# QCopterRCs_Sch.net
KiCad netlist of a schematic drawn in Altium Designer
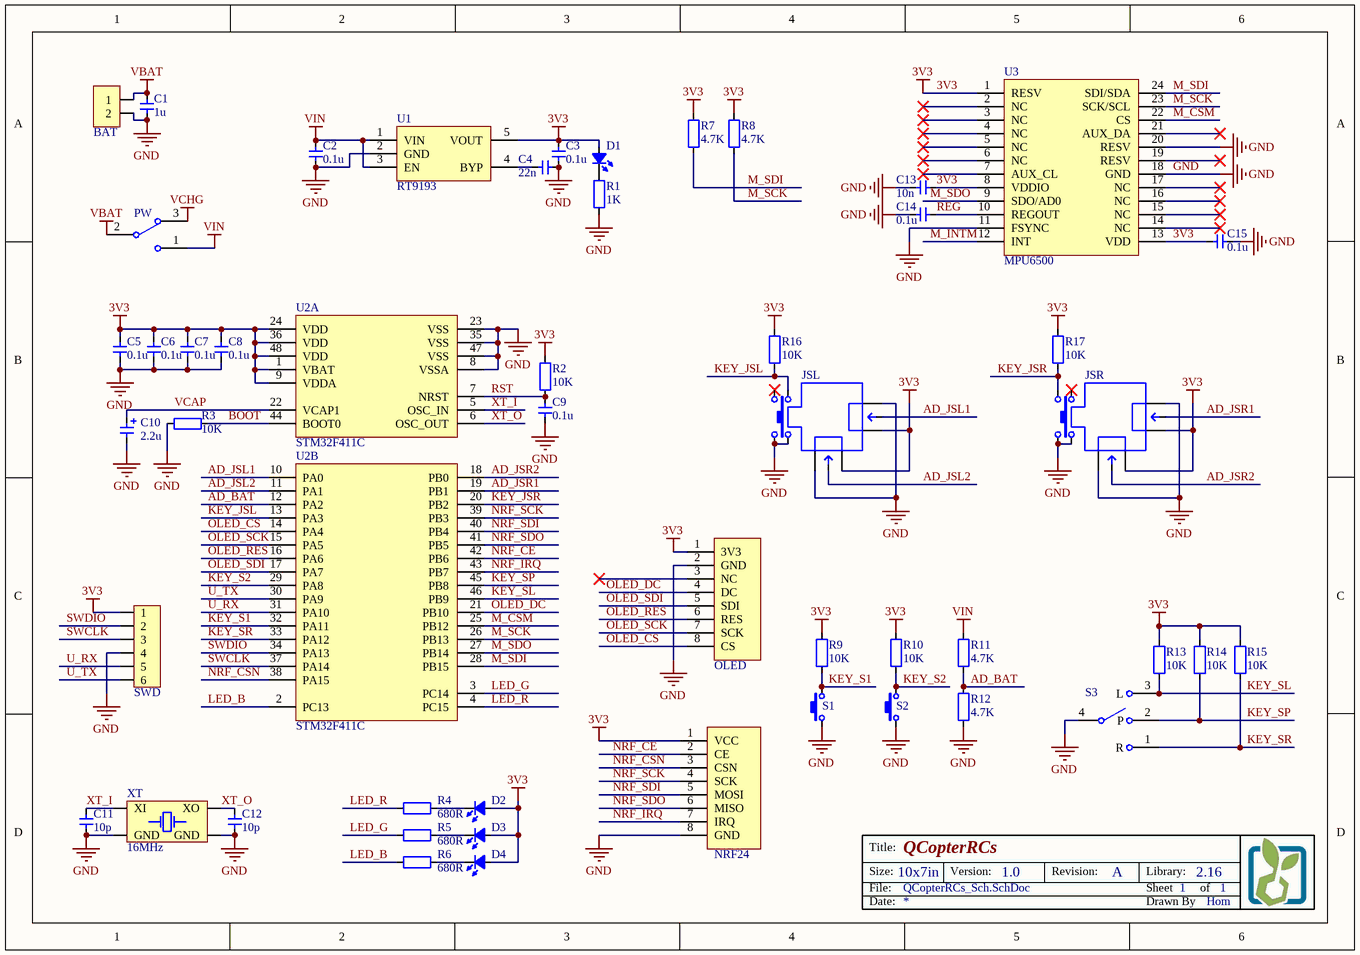
[diagram p0: QCopterRCs_Sch.SchDoc]

(export (version "E")
  (design (tool "Eeschema 10.0.6"))
  (components
    (comp (ref "BAT")
      (value "MX1.25_2P")
      (footprint "PCB_Connector:MX1.25_S90_2P")
      (description "MX")
      (libsource (lib "SCH_Connector") (part "MX1.25_2P"))
    )
    (comp (ref "C1")
      (value "1u")
      (footprint "PCB_PassiveCap:CAP_0603")
      (description "Capacitor")
      (fields (field (name "Comment") "Cap_0603"))
      (libsource (lib "SCH_Passive") (part "Cap_0603"))
    )
    (comp (ref "C2")
      (value "0.1u")
      (footprint "PCB_PassiveCap:CAP_0603")
      (description "Capacitor")
      (fields (field (name "Comment") "Cap_0603"))
      (libsource (lib "SCH_Passive") (part "Cap_0603"))
    )
    (comp (ref "C3")
      (value "0.1u")
      (footprint "PCB_PassiveCap:CAP_0603")
      (description "Capacitor")
      (fields (field (name "Comment") "Cap_0603"))
      (libsource (lib "SCH_Passive") (part "Cap_0603"))
    )
    (comp (ref "C4")
      (value "22n")
      (footprint "PCB_PassiveCap:CAP_0603")
      (description "Capacitor")
      (fields (field (name "Comment") "Cap_0603"))
      (libsource (lib "SCH_Passive") (part "Cap_0603"))
    )
    (comp (ref "C5")
      (value "0.1u")
      (footprint "PCB_PassiveCap:CAP_0603")
      (description "Capacitor")
      (fields (field (name "Comment") "Cap_0603"))
      (libsource (lib "SCH_Passive") (part "Cap_0603"))
    )
    (comp (ref "C6")
      (value "0.1u")
      (footprint "PCB_PassiveCap:CAP_0603")
      (description "Capacitor")
      (fields (field (name "Comment") "Cap_0603"))
      (libsource (lib "SCH_Passive") (part "Cap_0603"))
    )
    (comp (ref "C7")
      (value "0.1u")
      (footprint "PCB_PassiveCap:CAP_0603")
      (description "Capacitor")
      (fields (field (name "Comment") "Cap_0603"))
      (libsource (lib "SCH_Passive") (part "Cap_0603"))
    )
    (comp (ref "C8")
      (value "0.1u")
      (footprint "PCB_PassiveCap:CAP_0603")
      (description "Capacitor")
      (fields (field (name "Comment") "Cap_0603"))
      (libsource (lib "SCH_Passive") (part "Cap_0603"))
    )
    (comp (ref "C9")
      (value "0.1u")
      (footprint "PCB_PassiveCap:CAP_0603")
      (description "Capacitor")
      (fields (field (name "Comment") "Cap_0603"))
      (libsource (lib "SCH_Passive") (part "Cap_0603"))
    )
    (comp (ref "C10")
      (value "2.2u")
      (footprint "PCB_PassiveCap:CAP_TAN_P0805")
      (description "Capacitor")
      (fields (field (name "Comment") "Cap_Tan_0805"))
      (libsource (lib "SCH_Passive") (part "Cap_Tan_0805"))
    )
    (comp (ref "C11")
      (value "10p")
      (footprint "PCB_PassiveCap:CAP_0603")
      (description "Capacitor")
      (fields (field (name "Comment") "Cap_0603"))
      (libsource (lib "SCH_Passive") (part "Cap_0603"))
    )
    (comp (ref "C12")
      (value "10p")
      (footprint "PCB_PassiveCap:CAP_0603")
      (description "Capacitor")
      (fields (field (name "Comment") "Cap_0603"))
      (libsource (lib "SCH_Passive") (part "Cap_0603"))
    )
    (comp (ref "C13")
      (value "10n")
      (footprint "PCB_PassiveCap:CAP_0603")
      (description "Capacitor")
      (fields (field (name "Comment") "Cap_0603"))
      (libsource (lib "SCH_Passive") (part "Cap_0603"))
    )
    (comp (ref "C14")
      (value "0.1u")
      (footprint "PCB_PassiveCap:CAP_0603")
      (description "Capacitor")
      (fields (field (name "Comment") "Cap_0603"))
      (libsource (lib "SCH_Passive") (part "Cap_0603"))
    )
    (comp (ref "C15")
      (value "0.1u")
      (footprint "PCB_PassiveCap:CAP_0603")
      (description "Capacitor")
      (fields (field (name "Comment") "Cap_0603"))
      (libsource (lib "SCH_Passive") (part "Cap_0603"))
    )
    (comp (ref "D1")
      (value "LED_0603")
      (footprint "PCB_ActiveLED:LED_0603_YELLOW")
      (description "LED")
      (libsource (lib "SCH_Active") (part "LED_0603"))
    )
    (comp (ref "D2")
      (value "LED_0805")
      (footprint "PCB_ActiveLED:LED_0805_RED")
      (description "LED")
      (libsource (lib "SCH_Active") (part "LED_0805"))
    )
    (comp (ref "D3")
      (value "LED_0805")
      (footprint "PCB_ActiveLED:LED_0805_GREEN")
      (description "LED")
      (libsource (lib "SCH_Active") (part "LED_0805"))
    )
    (comp (ref "D4")
      (value "LED_0805")
      (footprint "PCB_ActiveLED:LED_0805_BLUE")
      (description "LED")
      (libsource (lib "SCH_Active") (part "LED_0805"))
    )
    (comp (ref "JSL")
      (value "JoyStick")
      (footprint "PCB_Switch:JoyStick")
      (libsource (lib "SCH_Switch") (part "JoyStick"))
    )
    (comp (ref "JSR")
      (value "JoyStick")
      (footprint "PCB_Switch:JoyStick")
      (libsource (lib "SCH_Switch") (part "JoyStick"))
    )
    (comp (ref "NRF24")
      (value "nRF24L01P_PA_LNA")
      (footprint "PCB_Module:NRF24L01P_PA_LNA")
      (description "Module")
      (libsource (lib "SCH_Module") (part "nRF24L01P_PA_LNA"))
    )
    (comp (ref "OLED")
      (value "OLED_1.5_128*128")
      (footprint "PCB_Module:OLED_1.5_128x128")
      (description "Module")
      (libsource (lib "SCH_Module") (part "OLED_1.5_128*128"))
    )
    (comp (ref "PW")
      (value "SwitchSPDT_2.8x6.6_90")
      (footprint "PCB_Switch:SwitchSPDT_2.8X6.6_90")
      (description "Switch")
      (libsource (lib "SCH_Switch") (part "SwitchSPDT_2.8x6.6_90"))
    )
    (comp (ref "R1")
      (value "1K")
      (footprint "PCB_PassiveRes:RES_0603")
      (description "Resistor")
      (fields (field (name "Comment") "Res_0603"))
      (libsource (lib "SCH_Passive") (part "Res_0603"))
    )
    (comp (ref "R2")
      (value "10K")
      (footprint "PCB_PassiveRes:RES_0603")
      (description "Resistor")
      (fields (field (name "Comment") "Res_0603"))
      (libsource (lib "SCH_Passive") (part "Res_0603"))
    )
    (comp (ref "R3")
      (value "10K")
      (footprint "PCB_PassiveRes:RES_0603")
      (description "Resistor")
      (fields (field (name "Comment") "Res_0603"))
      (libsource (lib "") (part "Res_0603_2"))
    )
    (comp (ref "R4")
      (value "680R")
      (footprint "PCB_PassiveRes:RES_0603")
      (description "Resistor")
      (fields (field (name "Comment") "Res_0603"))
      (libsource (lib "") (part "Res_0603_1"))
    )
    (comp (ref "R5")
      (value "680R")
      (footprint "PCB_PassiveRes:RES_0603")
      (description "Resistor")
      (fields (field (name "Comment") "Res_0603"))
      (libsource (lib "") (part "Res_0603_1"))
    )
    (comp (ref "R6")
      (value "680R")
      (footprint "PCB_PassiveRes:RES_0603")
      (description "Resistor")
      (fields (field (name "Comment") "Res_0603"))
      (libsource (lib "") (part "Res_0603_1"))
    )
    (comp (ref "R7")
      (value "4.7K")
      (footprint "PCB_PassiveRes:RES_0603")
      (description "Resistor")
      (fields (field (name "Comment") "Res_0603"))
      (libsource (lib "SCH_Passive") (part "Res_0603"))
    )
    (comp (ref "R8")
      (value "4.7K")
      (footprint "PCB_PassiveRes:RES_0603")
      (description "Resistor")
      (fields (field (name "Comment") "Res_0603"))
      (libsource (lib "SCH_Passive") (part "Res_0603"))
    )
    (comp (ref "R9")
      (value "10K")
      (footprint "PCB_PassiveRes:RES_0603")
      (description "Resistor")
      (fields (field (name "Comment") "Res_0603"))
      (libsource (lib "SCH_Passive") (part "Res_0603"))
    )
    (comp (ref "R10")
      (value "10K")
      (footprint "PCB_PassiveRes:RES_0603")
      (description "Resistor")
      (fields (field (name "Comment") "Res_0603"))
      (libsource (lib "SCH_Passive") (part "Res_0603"))
    )
    (comp (ref "R11")
      (value "4.7K")
      (footprint "PCB_PassiveRes:RES_0603")
      (description "Resistor")
      (fields (field (name "Comment") "Res_0603"))
      (libsource (lib "SCH_Passive") (part "Res_0603"))
    )
    (comp (ref "R12")
      (value "4.7K")
      (footprint "PCB_PassiveRes:RES_0603")
      (description "Resistor")
      (fields (field (name "Comment") "Res_0603"))
      (libsource (lib "SCH_Passive") (part "Res_0603"))
    )
    (comp (ref "R13")
      (value "10K")
      (footprint "PCB_PassiveRes:RES_0603")
      (description "Resistor")
      (fields (field (name "Comment") "Res_0603"))
      (libsource (lib "SCH_Passive") (part "Res_0603"))
    )
    (comp (ref "R14")
      (value "10K")
      (footprint "PCB_PassiveRes:RES_0603")
      (description "Resistor")
      (fields (field (name "Comment") "Res_0603"))
      (libsource (lib "SCH_Passive") (part "Res_0603"))
    )
    (comp (ref "R15")
      (value "10K")
      (footprint "PCB_PassiveRes:RES_0603")
      (description "Resistor")
      (fields (field (name "Comment") "Res_0603"))
      (libsource (lib "SCH_Passive") (part "Res_0603"))
    )
    (comp (ref "R16")
      (value "10K")
      (footprint "PCB_PassiveRes:RES_0603")
      (description "Resistor")
      (fields (field (name "Comment") "Res_0603"))
      (libsource (lib "SCH_Passive") (part "Res_0603"))
    )
    (comp (ref "R17")
      (value "10K")
      (footprint "PCB_PassiveRes:RES_0603")
      (description "Resistor")
      (fields (field (name "Comment") "Res_0603"))
      (libsource (lib "SCH_Passive") (part "Res_0603"))
    )
    (comp (ref "S1")
      (value "ButtonTACT_3x6x2.5_180")
      (footprint "PCB_Switch:ButtonTACT_3x6x2.5_180")
      (description "Button")
      (libsource (lib "SCH_Switch") (part "ButtonTACT_3x6x2.5_180"))
    )
    (comp (ref "S2")
      (value "ButtonTACT_3x6x2.5_180")
      (footprint "PCB_Switch:ButtonTACT_3x6x2.5_180")
      (description "Button")
      (libsource (lib "SCH_Switch") (part "ButtonTACT_3x6x2.5_180"))
    )
    (comp (ref "S3")
      (value "ButtonPushLever_11*12_90")
      (footprint "PCB_Switch:ButtonPushLever_11*12_90")
      (description "Button")
      (libsource (lib "SCH_Switch") (part "ButtonPushLever_11*12_90"))
    )
    (comp (ref "SWD")
      (value "HDR1x6_1.27")
      (footprint "PCB_ConnectorHDR:HDR1X6_1.27_180HF")
      (description "Header")
      (libsource (lib "SCH_ConnectorHDR") (part "HDR1x6_1.27"))
    )
    (comp (ref "U1")
      (value "RT9193")
      (footprint "PCB_IntegratedCircuit:SOT23-5")
      (description "Power")
      (libsource (lib "SCH_IntegratedCircuit") (part "RT9193"))
    )
    (comp (ref "U2")
      (value "STM32F411C")
      (footprint "PCB_IntegratedCircuit:QFN_P0.5_48")
      (description "MCU")
      (libsource (lib "SCH_IntegratedCircuit") (part "STM32F4x1C"))
    )
    (comp (ref "U3")
      (value "MPU6500")
      (footprint "PCB_IntegratedCircuit:QFN_P0.4_24")
      (description "Sensor Motion")
      (libsource (lib "SCH_IntegratedCircuit") (part "MPU925x"))
    )
    (comp (ref "XT")
      (value "16MHz")
      (footprint "PCB_Oscillator:XT_2520_4")
      (description "Crystal Oscillator")
      (fields (field (name "Comment") "XTAL_2520_4P"))
      (libsource (lib "SCH_Oscillator") (part "XTAL_2520_4P"))
    )
  )
  (nets
    (net (code "1") (name "/AD_BAT") (class "Default")
      (node (ref "R11") (pin "1") (pinfunction "1_1") (pintype "passive"))
      (node (ref "R12") (pin "2") (pinfunction "2_2") (pintype "passive"))
      (node (ref "U2") (pin "12") (pinfunction "PA2_12") (pintype "passive"))
    )
    (net (code "2") (name "/AD_JSL1") (class "Default")
      (node (ref "JSL") (pin "5") (pinfunction "5_5") (pintype "passive"))
      (node (ref "U2") (pin "10") (pinfunction "PA0_10") (pintype "passive"))
    )
    (net (code "3") (name "/AD_JSL2") (class "Default")
      (node (ref "JSL") (pin "2") (pinfunction "2_2") (pintype "passive"))
      (node (ref "U2") (pin "11") (pinfunction "PA1_11") (pintype "passive"))
    )
    (net (code "4") (name "/AD_JSR1") (class "Default")
      (node (ref "JSR") (pin "5") (pinfunction "5_5") (pintype "passive"))
      (node (ref "U2") (pin "19") (pinfunction "PB1_19") (pintype "passive"))
    )
    (net (code "5") (name "/AD_JSR2") (class "Default")
      (node (ref "JSR") (pin "2") (pinfunction "2_2") (pintype "passive"))
      (node (ref "U2") (pin "18") (pinfunction "PB0_18") (pintype "passive"))
    )
    (net (code "6") (name "/BOOT") (class "Default")
      (node (ref "R3") (pin "1") (pinfunction "1_1") (pintype "passive"))
      (node (ref "U2") (pin "44") (pinfunction "BOOT0_44") (pintype "passive"))
    )
    (net (code "7") (name "/KEY_JSL") (class "Default")
      (node (ref "JSL") (pin "9") (pinfunction "9_9") (pintype "passive"))
      (node (ref "R16") (pin "1") (pinfunction "1_1") (pintype "passive"))
      (node (ref "U2") (pin "13") (pinfunction "PA3_13") (pintype "passive"))
    )
    (net (code "8") (name "/KEY_JSR") (class "Default")
      (node (ref "JSR") (pin "7") (pinfunction "7_7") (pintype "passive"))
      (node (ref "R17") (pin "1") (pinfunction "1_1") (pintype "passive"))
      (node (ref "U2") (pin "20") (pinfunction "PB2_20") (pintype "passive"))
    )
    (net (code "9") (name "/KEY_S1") (class "Default")
      (node (ref "R9") (pin "1") (pinfunction "1_1") (pintype "passive"))
      (node (ref "S1") (pin "2") (pinfunction "2_2") (pintype "passive"))
      (node (ref "U2") (pin "32") (pinfunction "PA11_32") (pintype "passive"))
    )
    (net (code "10") (name "/KEY_S2") (class "Default")
      (node (ref "R10") (pin "1") (pinfunction "1_1") (pintype "passive"))
      (node (ref "S2") (pin "2") (pinfunction "2_2") (pintype "passive"))
      (node (ref "U2") (pin "29") (pinfunction "PA8_29") (pintype "passive"))
    )
    (net (code "11") (name "/KEY_SL") (class "Default")
      (node (ref "R13") (pin "1") (pinfunction "1_1") (pintype "passive"))
      (node (ref "S3") (pin "3") (pinfunction "L_3") (pintype "passive"))
      (node (ref "U2") (pin "46") (pinfunction "PB9_46") (pintype "passive"))
    )
    (net (code "12") (name "/KEY_SP") (class "Default")
      (node (ref "R14") (pin "1") (pinfunction "1_1") (pintype "passive"))
      (node (ref "S3") (pin "2") (pinfunction "P_2") (pintype "passive"))
      (node (ref "U2") (pin "45") (pinfunction "PB8_45") (pintype "passive"))
    )
    (net (code "13") (name "/KEY_SR") (class "Default")
      (node (ref "R15") (pin "1") (pinfunction "1_1") (pintype "passive"))
      (node (ref "S3") (pin "1") (pinfunction "R_1") (pintype "passive"))
      (node (ref "U2") (pin "33") (pinfunction "PA12_33") (pintype "passive"))
    )
    (net (code "14") (name "/LED_B") (class "Default")
      (node (ref "R6") (pin "1") (pinfunction "1_1") (pintype "passive"))
      (node (ref "U2") (pin "2") (pinfunction "PC13_2") (pintype "passive"))
    )
    (net (code "15") (name "/LED_G") (class "Default")
      (node (ref "R5") (pin "1") (pinfunction "1_1") (pintype "passive"))
      (node (ref "U2") (pin "3") (pinfunction "PC14_3") (pintype "passive"))
    )
    (net (code "16") (name "/LED_R") (class "Default")
      (node (ref "R4") (pin "1") (pinfunction "1_1") (pintype "passive"))
      (node (ref "U2") (pin "4") (pinfunction "PC15_4") (pintype "passive"))
    )
    (net (code "17") (name "/M_CSM") (class "Default")
      (node (ref "U2") (pin "25") (pinfunction "PB12_25") (pintype "passive"))
      (node (ref "U3") (pin "22") (pinfunction "CS_22") (pintype "passive"))
    )
    (net (code "18") (name "/M_INTM") (class "Default")
      (node (ref "U3") (pin "12") (pinfunction "INT_12") (pintype "passive"))
    )
    (net (code "19") (name "/M_SCK") (class "Default")
      (node (ref "R8") (pin "1") (pinfunction "1_1") (pintype "passive"))
      (node (ref "U2") (pin "26") (pinfunction "PB13_26") (pintype "passive"))
      (node (ref "U3") (pin "23") (pinfunction "SCK/SCL_23") (pintype "passive"))
    )
    (net (code "20") (name "/M_SDI") (class "Default")
      (node (ref "R7") (pin "1") (pinfunction "1_1") (pintype "passive"))
      (node (ref "U2") (pin "28") (pinfunction "PB15_28") (pintype "passive"))
      (node (ref "U3") (pin "24") (pinfunction "SDI/SDA_24") (pintype "passive"))
    )
    (net (code "21") (name "/M_SDO") (class "Default")
      (node (ref "U2") (pin "27") (pinfunction "PB14_27") (pintype "passive"))
      (node (ref "U3") (pin "9") (pinfunction "SDO/AD0_9") (pintype "passive"))
    )
    (net (code "22") (name "/NRF_CE") (class "Default")
      (node (ref "NRF24") (pin "2") (pinfunction "CE_2") (pintype "passive"))
      (node (ref "U2") (pin "42") (pinfunction "PB6_42") (pintype "passive"))
    )
    (net (code "23") (name "/NRF_CSN") (class "Default")
      (node (ref "NRF24") (pin "3") (pinfunction "CSN_3") (pintype "passive"))
      (node (ref "U2") (pin "38") (pinfunction "PA15_38") (pintype "passive"))
    )
    (net (code "24") (name "/NRF_IRQ") (class "Default")
      (node (ref "NRF24") (pin "7") (pinfunction "IRQ_7") (pintype "passive"))
      (node (ref "U2") (pin "43") (pinfunction "PB7_43") (pintype "passive"))
    )
    (net (code "25") (name "/NRF_SCK") (class "Default")
      (node (ref "NRF24") (pin "4") (pinfunction "SCK_4") (pintype "passive"))
      (node (ref "U2") (pin "39") (pinfunction "PB3_39") (pintype "passive"))
    )
    (net (code "26") (name "/NRF_SDI") (class "Default")
      (node (ref "NRF24") (pin "5") (pinfunction "MOSI_5") (pintype "passive"))
      (node (ref "U2") (pin "40") (pinfunction "PB4_40") (pintype "passive"))
    )
    (net (code "27") (name "/NRF_SDO") (class "Default")
      (node (ref "NRF24") (pin "6") (pinfunction "MISO_6") (pintype "passive"))
      (node (ref "U2") (pin "41") (pinfunction "PB5_41") (pintype "passive"))
    )
    (net (code "28") (name "/OLED_CS") (class "Default")
      (node (ref "OLED") (pin "8") (pinfunction "CS_8") (pintype "passive"))
      (node (ref "U2") (pin "14") (pinfunction "PA4_14") (pintype "passive"))
    )
    (net (code "29") (name "/OLED_DC") (class "Default")
      (node (ref "OLED") (pin "4") (pinfunction "DC_4") (pintype "passive"))
      (node (ref "U2") (pin "21") (pinfunction "PB10_21") (pintype "passive"))
    )
    (net (code "30") (name "/OLED_RES") (class "Default")
      (node (ref "OLED") (pin "6") (pinfunction "RES_6") (pintype "passive"))
      (node (ref "U2") (pin "16") (pinfunction "PA6_16") (pintype "passive"))
    )
    (net (code "31") (name "/OLED_SCK") (class "Default")
      (node (ref "OLED") (pin "7") (pinfunction "SCK_7") (pintype "passive"))
      (node (ref "U2") (pin "15") (pinfunction "PA5_15") (pintype "passive"))
    )
    (net (code "32") (name "/OLED_SDI") (class "Default")
      (node (ref "OLED") (pin "5") (pinfunction "SDI_5") (pintype "passive"))
      (node (ref "U2") (pin "17") (pinfunction "PA7_17") (pintype "passive"))
    )
    (net (code "33") (name "/REG") (class "Default")
      (node (ref "C14") (pin "1") (pinfunction "1_1") (pintype "passive"))
      (node (ref "U3") (pin "10") (pinfunction "REGOUT_10") (pintype "passive"))
    )
    (net (code "34") (name "/RST") (class "Default")
      (node (ref "C9") (pin "2") (pinfunction "2_2") (pintype "passive"))
      (node (ref "R2") (pin "1") (pinfunction "1_1") (pintype "passive"))
      (node (ref "U2") (pin "7") (pinfunction "NRST_7") (pintype "passive"))
    )
    (net (code "35") (name "/SWCLK") (class "Default")
      (node (ref "SWD") (pin "3") (pinfunction "3_3") (pintype "passive"))
      (node (ref "U2") (pin "37") (pinfunction "PA14_37") (pintype "passive"))
    )
    (net (code "36") (name "/SWDIO") (class "Default")
      (node (ref "SWD") (pin "2") (pinfunction "2_2") (pintype "passive"))
      (node (ref "U2") (pin "34") (pinfunction "PA13_34") (pintype "passive"))
    )
    (net (code "37") (name "/U_RX") (class "Default")
      (node (ref "SWD") (pin "5") (pinfunction "5_5") (pintype "passive"))
      (node (ref "U2") (pin "31") (pinfunction "PA10_31") (pintype "passive"))
    )
    (net (code "38") (name "/U_TX") (class "Default")
      (node (ref "SWD") (pin "6") (pinfunction "6_6") (pintype "passive"))
      (node (ref "U2") (pin "30") (pinfunction "PA9_30") (pintype "passive"))
    )
    (net (code "39") (name "/VCAP") (class "Default")
      (node (ref "C10") (pin "1") (pinfunction "1_1") (pintype "passive"))
      (node (ref "U2") (pin "22") (pinfunction "VCAP1_22") (pintype "passive"))
    )
    (net (code "40") (name "/XT_I") (class "Default")
      (node (ref "C11") (pin "2") (pinfunction "2_2") (pintype "passive"))
      (node (ref "U2") (pin "5") (pinfunction "OSC_IN_5") (pintype "passive"))
      (node (ref "XT") (pin "1") (pinfunction "XI_1") (pintype "passive"))
    )
    (net (code "41") (name "/XT_O") (class "Default")
      (node (ref "C12") (pin "2") (pinfunction "2_2") (pintype "passive"))
      (node (ref "U2") (pin "6") (pinfunction "OSC_OUT_6") (pintype "passive"))
      (node (ref "XT") (pin "3") (pinfunction "XO_3") (pintype "passive"))
    )
    (net (code "42") (name "3V3") (class "Default")
      (node (ref "C13") (pin "1") (pinfunction "1_1") (pintype "passive"))
      (node (ref "C15") (pin "2") (pinfunction "2_2") (pintype "passive"))
      (node (ref "C3") (pin "2") (pinfunction "2_2") (pintype "passive"))
      (node (ref "C5") (pin "2") (pinfunction "2_2") (pintype "passive"))
      (node (ref "C6") (pin "2") (pinfunction "2_2") (pintype "passive"))
      (node (ref "C7") (pin "2") (pinfunction "2_2") (pintype "passive"))
      (node (ref "C8") (pin "2") (pinfunction "2_2") (pintype "passive"))
      (node (ref "D1") (pin "1") (pinfunction "A_1") (pintype "passive"))
      (node (ref "D2") (pin "1") (pinfunction "A_1") (pintype "passive"))
      (node (ref "D3") (pin "1") (pinfunction "A_1") (pintype "passive"))
      (node (ref "D4") (pin "1") (pinfunction "A_1") (pintype "passive"))
      (node (ref "JSL") (pin "3") (pinfunction "3_3") (pintype "passive"))
      (node (ref "JSL") (pin "4") (pinfunction "4_4") (pintype "passive"))
      (node (ref "JSR") (pin "3") (pinfunction "3_3") (pintype "passive"))
      (node (ref "JSR") (pin "4") (pinfunction "4_4") (pintype "passive"))
      (node (ref "NRF24") (pin "1") (pinfunction "VCC_1") (pintype "passive"))
      (node (ref "OLED") (pin "1") (pinfunction "3V3_1") (pintype "passive"))
      (node (ref "R10") (pin "2") (pinfunction "2_2") (pintype "passive"))
      (node (ref "R13") (pin "2") (pinfunction "2_2") (pintype "passive"))
      (node (ref "R14") (pin "2") (pinfunction "2_2") (pintype "passive"))
      (node (ref "R15") (pin "2") (pinfunction "2_2") (pintype "passive"))
      (node (ref "R16") (pin "2") (pinfunction "2_2") (pintype "passive"))
      (node (ref "R17") (pin "2") (pinfunction "2_2") (pintype "passive"))
      (node (ref "R2") (pin "2") (pinfunction "2_2") (pintype "passive"))
      (node (ref "R7") (pin "2") (pinfunction "2_2") (pintype "passive"))
      (node (ref "R8") (pin "2") (pinfunction "2_2") (pintype "passive"))
      (node (ref "R9") (pin "2") (pinfunction "2_2") (pintype "passive"))
      (node (ref "SWD") (pin "1") (pinfunction "1_1") (pintype "passive"))
      (node (ref "U1") (pin "5") (pinfunction "VOUT_5") (pintype "passive"))
      (node (ref "U2") (pin "1") (pinfunction "VBAT_1") (pintype "passive"))
      (node (ref "U2") (pin "24") (pinfunction "VDD_24") (pintype "passive"))
      (node (ref "U2") (pin "36") (pinfunction "VDD_36") (pintype "passive"))
      (node (ref "U2") (pin "48") (pinfunction "VDD_48") (pintype "passive"))
      (node (ref "U2") (pin "9") (pinfunction "VDDA_9") (pintype "passive"))
      (node (ref "U3") (pin "1") (pinfunction "RESV_1") (pintype "passive"))
      (node (ref "U3") (pin "13") (pinfunction "VDD_13") (pintype "passive"))
      (node (ref "U3") (pin "8") (pinfunction "VDDIO_8") (pintype "passive"))
    )
    (net (code "43") (name "GND") (class "Default")
      (node (ref "BAT") (pin "2") (pinfunction "2_2") (pintype "passive"))
      (node (ref "C1") (pin "1") (pinfunction "1_1") (pintype "passive"))
      (node (ref "C10") (pin "2") (pinfunction "2_2") (pintype "passive"))
      (node (ref "C11") (pin "1") (pinfunction "1_1") (pintype "passive"))
      (node (ref "C12") (pin "1") (pinfunction "1_1") (pintype "passive"))
      (node (ref "C13") (pin "2") (pinfunction "2_2") (pintype "passive"))
      (node (ref "C14") (pin "2") (pinfunction "2_2") (pintype "passive"))
      (node (ref "C15") (pin "1") (pinfunction "1_1") (pintype "passive"))
      (node (ref "C2") (pin "1") (pinfunction "1_1") (pintype "passive"))
      (node (ref "C3") (pin "1") (pinfunction "1_1") (pintype "passive"))
      (node (ref "C4") (pin "1") (pinfunction "1_1") (pintype "passive"))
      (node (ref "C5") (pin "1") (pinfunction "1_1") (pintype "passive"))
      (node (ref "C6") (pin "1") (pinfunction "1_1") (pintype "passive"))
      (node (ref "C7") (pin "1") (pinfunction "1_1") (pintype "passive"))
      (node (ref "C8") (pin "1") (pinfunction "1_1") (pintype "passive"))
      (node (ref "C9") (pin "1") (pinfunction "1_1") (pintype "passive"))
      (node (ref "JSL") (pin "1") (pinfunction "1_1") (pintype "passive"))
      (node (ref "JSL") (pin "10") (pinfunction "10_10") (pintype "passive"))
      (node (ref "JSL") (pin "6") (pinfunction "6_6") (pintype "passive"))
      (node (ref "JSL") (pin "8") (pinfunction "8_8") (pintype "passive"))
      (node (ref "JSR") (pin "1") (pinfunction "1_1") (pintype "passive"))
      (node (ref "JSR") (pin "10") (pinfunction "10_10") (pintype "passive"))
      (node (ref "JSR") (pin "6") (pinfunction "6_6") (pintype "passive"))
      (node (ref "JSR") (pin "8") (pinfunction "8_8") (pintype "passive"))
      (node (ref "NRF24") (pin "8") (pinfunction "GND_8") (pintype "passive"))
      (node (ref "OLED") (pin "2") (pinfunction "GND_2") (pintype "passive"))
      (node (ref "R1") (pin "1") (pinfunction "1_1") (pintype "passive"))
      (node (ref "R12") (pin "1") (pinfunction "1_1") (pintype "passive"))
      (node (ref "R3") (pin "2") (pinfunction "2_2") (pintype "passive"))
      (node (ref "S1") (pin "1") (pinfunction "1_1") (pintype "passive"))
      (node (ref "S2") (pin "1") (pinfunction "1_1") (pintype "passive"))
      (node (ref "S3") (pin "4") (pinfunction "4_4") (pintype "passive"))
      (node (ref "SWD") (pin "4") (pinfunction "4_4") (pintype "passive"))
      (node (ref "U1") (pin "2") (pinfunction "GND_2") (pintype "passive"))
      (node (ref "U2") (pin "23") (pinfunction "VSS_23") (pintype "passive"))
      (node (ref "U2") (pin "35") (pinfunction "VSS_35") (pintype "passive"))
      (node (ref "U2") (pin "47") (pinfunction "VSS_47") (pintype "passive"))
      (node (ref "U2") (pin "8") (pinfunction "VSSA_8") (pintype "passive"))
      (node (ref "U3") (pin "11") (pinfunction "FSYNC_11") (pintype "passive"))
      (node (ref "U3") (pin "18") (pinfunction "GND_18") (pintype "passive"))
      (node (ref "U3") (pin "20") (pinfunction "RESV_20") (pintype "passive"))
      (node (ref "XT") (pin "2") (pinfunction "GND_2") (pintype "passive"))
      (node (ref "XT") (pin "4") (pinfunction "GND_4") (pintype "passive"))
    )
    (net (code "44") (name "Net-(D1-K)") (class "Default")
      (node (ref "D1") (pin "2") (pinfunction "K_2") (pintype "passive"))
      (node (ref "R1") (pin "2") (pinfunction "2_2") (pintype "passive"))
    )
    (net (code "45") (name "Net-(D2-K)") (class "Default")
      (node (ref "D2") (pin "2") (pinfunction "K_2") (pintype "passive"))
      (node (ref "R4") (pin "2") (pinfunction "2_2") (pintype "passive"))
    )
    (net (code "46") (name "Net-(D3-K)") (class "Default")
      (node (ref "D3") (pin "2") (pinfunction "K_2") (pintype "passive"))
      (node (ref "R5") (pin "2") (pinfunction "2_2") (pintype "passive"))
    )
    (net (code "47") (name "Net-(D4-K)") (class "Default")
      (node (ref "D4") (pin "2") (pinfunction "K_2") (pintype "passive"))
      (node (ref "R6") (pin "2") (pinfunction "2_2") (pintype "passive"))
    )
    (net (code "48") (name "Net-(U1-BYP)") (class "Default")
      (node (ref "C4") (pin "2") (pinfunction "2_2") (pintype "passive"))
      (node (ref "U1") (pin "4") (pinfunction "BYP_4") (pintype "passive"))
    )
    (net (code "49") (name "VBAT") (class "Default")
      (node (ref "BAT") (pin "1") (pinfunction "1_1") (pintype "passive"))
      (node (ref "C1") (pin "2") (pinfunction "2_2") (pintype "passive"))
      (node (ref "PW") (pin "2") (pinfunction "2_2") (pintype "passive"))
    )
    (net (code "50") (name "VCHG") (class "Default")
      (node (ref "PW") (pin "3") (pinfunction "3_3") (pintype "passive"))
    )
    (net (code "51") (name "VIN") (class "Default")
      (node (ref "C2") (pin "2") (pinfunction "2_2") (pintype "passive"))
      (node (ref "PW") (pin "1") (pinfunction "1_1") (pintype "passive"))
      (node (ref "R11") (pin "2") (pinfunction "2_2") (pintype "passive"))
      (node (ref "U1") (pin "1") (pinfunction "VIN_1") (pintype "passive"))
      (node (ref "U1") (pin "3") (pinfunction "EN_3") (pintype "power_in"))
    )
    (net (code "52") (name "unconnected-(JSL-Pad7)") (class "Default")
      (node (ref "JSL") (pin "7") (pinfunction "7_7") (pintype "passive+no_connect"))
    )
    (net (code "53") (name "unconnected-(JSR-Pad9)") (class "Default")
      (node (ref "JSR") (pin "9") (pinfunction "9_9") (pintype "passive+no_connect"))
    )
    (net (code "54") (name "unconnected-(OLED-NC-Pad3)") (class "Default")
      (node (ref "OLED") (pin "3") (pinfunction "NC_3") (pintype "passive+no_connect"))
    )
    (net (code "55") (name "unconnected-(U3-AUX_CL-Pad7)") (class "Default")
      (node (ref "U3") (pin "7") (pinfunction "AUX_CL_7") (pintype "passive+no_connect"))
    )
    (net (code "56") (name "unconnected-(U3-AUX_DA-Pad21)") (class "Default")
      (node (ref "U3") (pin "21") (pinfunction "AUX_DA_21") (pintype "passive+no_connect"))
    )
    (net (code "57") (name "unconnected-(U3-NC-Pad2)") (class "Default")
      (node (ref "U3") (pin "2") (pinfunction "NC_2") (pintype "passive+no_connect"))
    )
    (net (code "58") (name "unconnected-(U3-NC-Pad3)") (class "Default")
      (node (ref "U3") (pin "3") (pinfunction "NC_3") (pintype "passive+no_connect"))
    )
    (net (code "59") (name "unconnected-(U3-NC-Pad4)") (class "Default")
      (node (ref "U3") (pin "4") (pinfunction "NC_4") (pintype "passive+no_connect"))
    )
    (net (code "60") (name "unconnected-(U3-NC-Pad5)") (class "Default")
      (node (ref "U3") (pin "5") (pinfunction "NC_5") (pintype "passive+no_connect"))
    )
    (net (code "61") (name "unconnected-(U3-NC-Pad6)") (class "Default")
      (node (ref "U3") (pin "6") (pinfunction "NC_6") (pintype "passive+no_connect"))
    )
    (net (code "62") (name "unconnected-(U3-NC-Pad14)") (class "Default")
      (node (ref "U3") (pin "14") (pinfunction "NC_14") (pintype "passive+no_connect"))
    )
    (net (code "63") (name "unconnected-(U3-NC-Pad15)") (class "Default")
      (node (ref "U3") (pin "15") (pinfunction "NC_15") (pintype "passive+no_connect"))
    )
    (net (code "64") (name "unconnected-(U3-NC-Pad16)") (class "Default")
      (node (ref "U3") (pin "16") (pinfunction "NC_16") (pintype "passive+no_connect"))
    )
    (net (code "65") (name "unconnected-(U3-NC-Pad17)") (class "Default")
      (node (ref "U3") (pin "17") (pinfunction "NC_17") (pintype "passive+no_connect"))
    )
    (net (code "66") (name "unconnected-(U3-RESV-Pad19)") (class "Default")
      (node (ref "U3") (pin "19") (pinfunction "RESV_19") (pintype "passive+no_connect"))
    )
  )
)
